# Power_Supply.net
KiCad netlist of a schematic drawn in Altium Designer
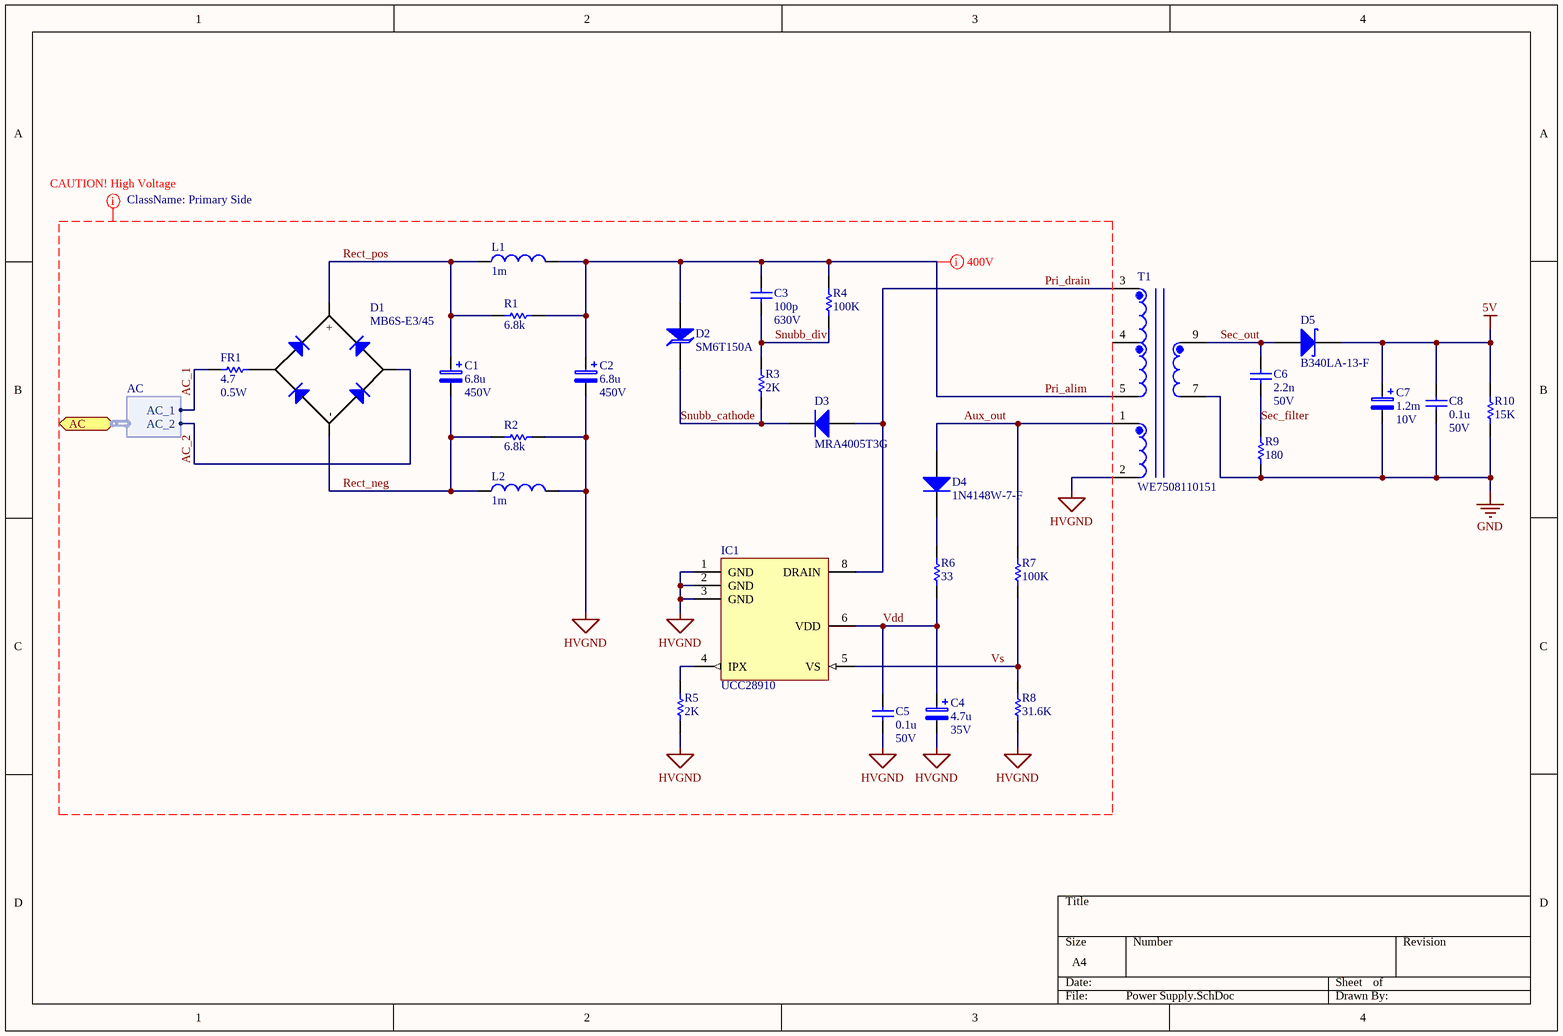
[diagram p0: Power Supply.SchDoc]

(export (version "E")
  (design (tool "Eeschema 10.0.6"))
  (components
    (comp (ref "C1")
      (value "6.8u")
      (footprint "CRADIAL-5mm-16mm")
      (description "Polarized Capacitor")
      (fields (field (name "RATED VOLTAGE") "450V"))
      (libsource (lib "Common Devices") (part "Pol Capacitor"))
    )
    (comp (ref "C2")
      (value "6.8u")
      (footprint "CRADIAL-5mm-16mm")
      (description "Polarized Capacitor")
      (fields (field (name "RATED VOLTAGE") "450V"))
      (libsource (lib "Common Devices") (part "Pol Capacitor"))
    )
    (comp (ref "C3")
      (value "100p")
      (footprint "C1206")
      (description "Capacitor")
      (fields (field (name "RATED VOLTAGE") "630V"))
      (libsource (lib "Common Devices") (part "Capacitor"))
    )
    (comp (ref "C4")
      (value "4.7u")
      (footprint "CAPAE5543X54N")
      (description "Polarized Capacitor")
      (fields (field (name "RATED VOLTAGE") "35V"))
      (libsource (lib "Common Devices") (part "Pol Capacitor"))
    )
    (comp (ref "C5")
      (value "0.1u")
      (footprint "C1206")
      (description "Capacitor")
      (fields (field (name "RATED VOLTAGE") "50V"))
      (libsource (lib "Common Devices") (part "Capacitor"))
    )
    (comp (ref "C6")
      (value "2.2n")
      (footprint "C1206")
      (description "Capacitor")
      (fields (field (name "RATED VOLTAGE") "50V"))
      (libsource (lib "Common Devices") (part "Capacitor"))
    )
    (comp (ref "C7")
      (value "1.2m")
      (footprint "CRADIAL-5mm-20mm")
      (description "Polarized Capacitor")
      (fields (field (name "RATED VOLTAGE") "10V"))
      (libsource (lib "Common Devices") (part "Pol Capacitor"))
    )
    (comp (ref "C8")
      (value "0.1u")
      (footprint "C1206")
      (description "Capacitor")
      (fields (field (name "RATED VOLTAGE") "50V"))
      (libsource (lib "Common Devices") (part "Capacitor"))
    )
    (comp (ref "D1")
      (value "MB6S-E3/45")
      (footprint "SOP250P670X290-4N")
      (description "Diode, Bridge Rectifier")
      (libsource (lib "Docking Station") (part "MB6S-E3/45"))
    )
    (comp (ref "D2")
      (value "SM6T150A")
      (footprint "SMB")
      (description "Diode, Transient Voltage Suppresor, 150V, 600W")
      (libsource (lib "Docking Station") (part "SM6T150A"))
    )
    (comp (ref "D3")
      (value "MRA4005T3G")
      (footprint "SMA")
      (description "Diode, Standard, 1A")
      (libsource (lib "Docking Station") (part "MRA4005T3G"))
    )
    (comp (ref "D4")
      (value "1N4148W-7-F")
      (footprint "SOD123")
      (description "Diode, Switch, 300mA, 100V")
      (libsource (lib "Docking Station") (part "1N4148W-7-F"))
    )
    (comp (ref "D5")
      (value "B340LA-13-F")
      (footprint "SMA")
      (description "Diode, Schottky, 40V, 3A")
      (libsource (lib "Docking Station") (part "B340LA-13-F"))
    )
    (comp (ref "FR1")
      (value "4.7")
      (footprint "RAXIAL-10mm-0.8mm")
      (description "Resistor, Fuse")
      (fields (field (name "POWER") "0.5W"))
      (libsource (lib "Common Devices") (part "Fuse Resistor"))
    )
    (comp (ref "IC1")
      (value "UCC28910")
      (footprint "SOIC127P600X175-7N")
      (description "700V Flyback Switcher with Constant-Voltage Constant-Current and Primary-side Control")
      (libsource (lib "Docking Station") (part "UCC28910"))
    )
    (comp (ref "L1")
      (value "1m")
      (footprint "INDUCTOR-5MM")
      (description "Inductor")
      (libsource (lib "Common Devices") (part "Inductor"))
    )
    (comp (ref "L2")
      (value "1m")
      (footprint "INDUCTOR-5MM")
      (description "Inductor")
      (libsource (lib "Common Devices") (part "Inductor"))
    )
    (comp (ref "R1")
      (value "6.8k")
      (footprint "R1206")
      (description "Resistor")
      (libsource (lib "Common Devices") (part "Resistor"))
    )
    (comp (ref "R2")
      (value "6.8k")
      (footprint "R1206")
      (description "Resistor")
      (libsource (lib "Common Devices") (part "Resistor"))
    )
    (comp (ref "R3")
      (value "2K")
      (footprint "R1206")
      (description "Resistor")
      (libsource (lib "Common Devices") (part "Resistor"))
    )
    (comp (ref "R4")
      (value "100K")
      (footprint "R1206")
      (description "Resistor")
      (libsource (lib "Common Devices") (part "Resistor"))
    )
    (comp (ref "R5")
      (value "2K")
      (footprint "R1206")
      (description "Resistor")
      (libsource (lib "Common Devices") (part "Resistor"))
    )
    (comp (ref "R6")
      (value "33")
      (footprint "R1206")
      (description "Resistor")
      (libsource (lib "Common Devices") (part "Resistor"))
    )
    (comp (ref "R7")
      (value "100K")
      (footprint "R1206")
      (description "Resistor")
      (libsource (lib "Common Devices") (part "Resistor"))
    )
    (comp (ref "R8")
      (value "31.6K")
      (footprint "R1206")
      (description "Resistor")
      (libsource (lib "Common Devices") (part "Resistor"))
    )
    (comp (ref "R9")
      (value "180")
      (footprint "R1206")
      (description "Resistor")
      (libsource (lib "Common Devices") (part "Resistor"))
    )
    (comp (ref "R10")
      (value "15K")
      (footprint "R1206")
      (description "Resistor")
      (libsource (lib "Common Devices") (part "Resistor"))
    )
    (comp (ref "T1")
      (value "WE7508110151")
      (footprint "WE7508110151")
      (description "Transformer, Flyback")
      (libsource (lib "Docking Station") (part "WE7508110151"))
    )
  )
  (nets
    (net (code "2") (name "/AC_1") (class "Default")
      (node (ref "FR1") (pin "1") (pinfunction "1_1") (pintype "passive"))
    )
    (net (code "3") (name "/AC_2") (class "Default")
      (node (ref "D1") (pin "2") (pinfunction "AC_2") (pintype "passive"))
    )
    (net (code "4") (name "/Aux_out") (class "Default")
      (node (ref "D4") (pin "1") (pinfunction "A_1") (pintype "passive"))
      (node (ref "R7") (pin "2") (pinfunction "2_2") (pintype "passive"))
      (node (ref "T1") (pin "1") (pinfunction "Aux1_1") (pintype "passive"))
    )
    (net (code "5") (name "/Pri_alim") (class "Default")
      (node (ref "C2") (pin "1") (pinfunction "1_1") (pintype "passive"))
      (node (ref "C3") (pin "2") (pinfunction "2_2") (pintype "passive"))
      (node (ref "D2") (pin "1") (pinfunction "A_1") (pintype "passive"))
      (node (ref "L1") (pin "2") (pinfunction "2_2") (pintype "passive"))
      (node (ref "R1") (pin "2") (pinfunction "2_2") (pintype "passive"))
      (node (ref "R4") (pin "2") (pinfunction "2_2") (pintype "passive"))
      (node (ref "T1") (pin "5") (pinfunction "Pri3_5") (pintype "passive"))
    )
    (net (code "6") (name "/Pri_drain") (class "Default")
      (node (ref "D3") (pin "1") (pinfunction "A_1") (pintype "passive"))
      (node (ref "IC1") (pin "8") (pinfunction "DRAIN_8") (pintype "passive"))
      (node (ref "T1") (pin "3") (pinfunction "Pri1_3") (pintype "passive"))
    )
    (net (code "7") (name "/Rect_neg") (class "Default")
      (node (ref "C1") (pin "2") (pinfunction "2_2") (pintype "passive"))
      (node (ref "D1") (pin "4") (pinfunction "-_4") (pintype "passive"))
      (node (ref "L2") (pin "1") (pinfunction "1_1") (pintype "passive"))
      (node (ref "R2") (pin "1") (pinfunction "1_1") (pintype "passive"))
    )
    (net (code "8") (name "/Rect_pos") (class "Default")
      (node (ref "C1") (pin "1") (pinfunction "1_1") (pintype "passive"))
      (node (ref "D1") (pin "3") (pinfunction "+_3") (pintype "passive"))
      (node (ref "L1") (pin "1") (pinfunction "1_1") (pintype "passive"))
      (node (ref "R1") (pin "1") (pinfunction "1_1") (pintype "passive"))
    )
    (net (code "9") (name "/Sec_filter") (class "Default")
      (node (ref "C6") (pin "1") (pinfunction "1_1") (pintype "passive"))
      (node (ref "R9") (pin "2") (pinfunction "2_2") (pintype "passive"))
    )
    (net (code "10") (name "/Sec_out") (class "Default")
      (node (ref "C6") (pin "2") (pinfunction "2_2") (pintype "passive"))
      (node (ref "D5") (pin "1") (pinfunction "A_1") (pintype "passive"))
      (node (ref "T1") (pin "9") (pinfunction "Sec1_9") (pintype "passive"))
    )
    (net (code "11") (name "/Snubb_cathode") (class "Default")
      (node (ref "D2") (pin "2") (pinfunction "K_2") (pintype "passive"))
      (node (ref "D3") (pin "2") (pinfunction "K_2") (pintype "passive"))
      (node (ref "R3") (pin "1") (pinfunction "1_1") (pintype "passive"))
    )
    (net (code "12") (name "/Snubb_div") (class "Default")
      (node (ref "C3") (pin "1") (pinfunction "1_1") (pintype "passive"))
      (node (ref "R3") (pin "2") (pinfunction "2_2") (pintype "passive"))
      (node (ref "R4") (pin "1") (pinfunction "1_1") (pintype "passive"))
    )
    (net (code "13") (name "/Vdd") (class "Default")
      (node (ref "C4") (pin "1") (pinfunction "1_1") (pintype "passive"))
      (node (ref "C5") (pin "2") (pinfunction "2_2") (pintype "passive"))
      (node (ref "IC1") (pin "6") (pinfunction "VDD_6") (pintype "power_in"))
      (node (ref "R6") (pin "1") (pinfunction "1_1") (pintype "passive"))
    )
    (net (code "14") (name "/Vs") (class "Default")
      (node (ref "IC1") (pin "5") (pinfunction "VS_5") (pintype "input"))
      (node (ref "R7") (pin "1") (pinfunction "1_1") (pintype "passive"))
      (node (ref "R8") (pin "2") (pinfunction "2_2") (pintype "passive"))
    )
    (net (code "16") (name "5V") (class "Default")
      (node (ref "C7") (pin "1") (pinfunction "1_1") (pintype "passive"))
      (node (ref "C8") (pin "2") (pinfunction "2_2") (pintype "passive"))
      (node (ref "D5") (pin "2") (pinfunction "K_2") (pintype "passive"))
      (node (ref "R10") (pin "2") (pinfunction "2_2") (pintype "passive"))
    )
    (net (code "17") (name "GND") (class "Default")
      (node (ref "C7") (pin "2") (pinfunction "2_2") (pintype "passive"))
      (node (ref "C8") (pin "1") (pinfunction "1_1") (pintype "passive"))
      (node (ref "R10") (pin "1") (pinfunction "1_1") (pintype "passive"))
      (node (ref "R9") (pin "1") (pinfunction "1_1") (pintype "passive"))
      (node (ref "T1") (pin "7") (pinfunction "Sec2_7") (pintype "passive"))
    )
    (net (code "18") (name "HVGND") (class "Default")
      (node (ref "C2") (pin "2") (pinfunction "2_2") (pintype "passive"))
      (node (ref "C4") (pin "2") (pinfunction "2_2") (pintype "passive"))
      (node (ref "C5") (pin "1") (pinfunction "1_1") (pintype "passive"))
      (node (ref "IC1") (pin "1") (pinfunction "GND_1") (pintype "power_in"))
      (node (ref "IC1") (pin "2") (pinfunction "GND_2") (pintype "power_in"))
      (node (ref "IC1") (pin "3") (pinfunction "GND_3") (pintype "power_in"))
      (node (ref "L2") (pin "2") (pinfunction "2_2") (pintype "passive"))
      (node (ref "R2") (pin "2") (pinfunction "2_2") (pintype "passive"))
      (node (ref "R5") (pin "1") (pinfunction "1_1") (pintype "passive"))
      (node (ref "R8") (pin "1") (pinfunction "1_1") (pintype "passive"))
      (node (ref "T1") (pin "2") (pinfunction "Aux2_2") (pintype "passive"))
    )
    (net (code "19") (name "Net-(D1-AC-Pad1)") (class "Default")
      (node (ref "D1") (pin "1") (pinfunction "AC_1") (pintype "passive"))
      (node (ref "FR1") (pin "2") (pinfunction "2_2") (pintype "passive"))
    )
    (net (code "20") (name "Net-(D4-K)") (class "Default")
      (node (ref "D4") (pin "2") (pinfunction "K_2") (pintype "passive"))
      (node (ref "R6") (pin "2") (pinfunction "2_2") (pintype "passive"))
    )
    (net (code "21") (name "Net-(IC1-IPX)") (class "Default")
      (node (ref "IC1") (pin "4") (pinfunction "IPX_4") (pintype "output"))
      (node (ref "R5") (pin "2") (pinfunction "2_2") (pintype "passive"))
    )
    (net (code "22") (name "unconnected-(T1-Pri2-Pad4)") (class "Default")
      (node (ref "T1") (pin "4") (pinfunction "Pri2_4") (pintype "passive"))
    )
  )
)
